# PROC051D_QSPI_Flash_Reference.net
KiCad netlist of a schematic drawn in Altium Designer
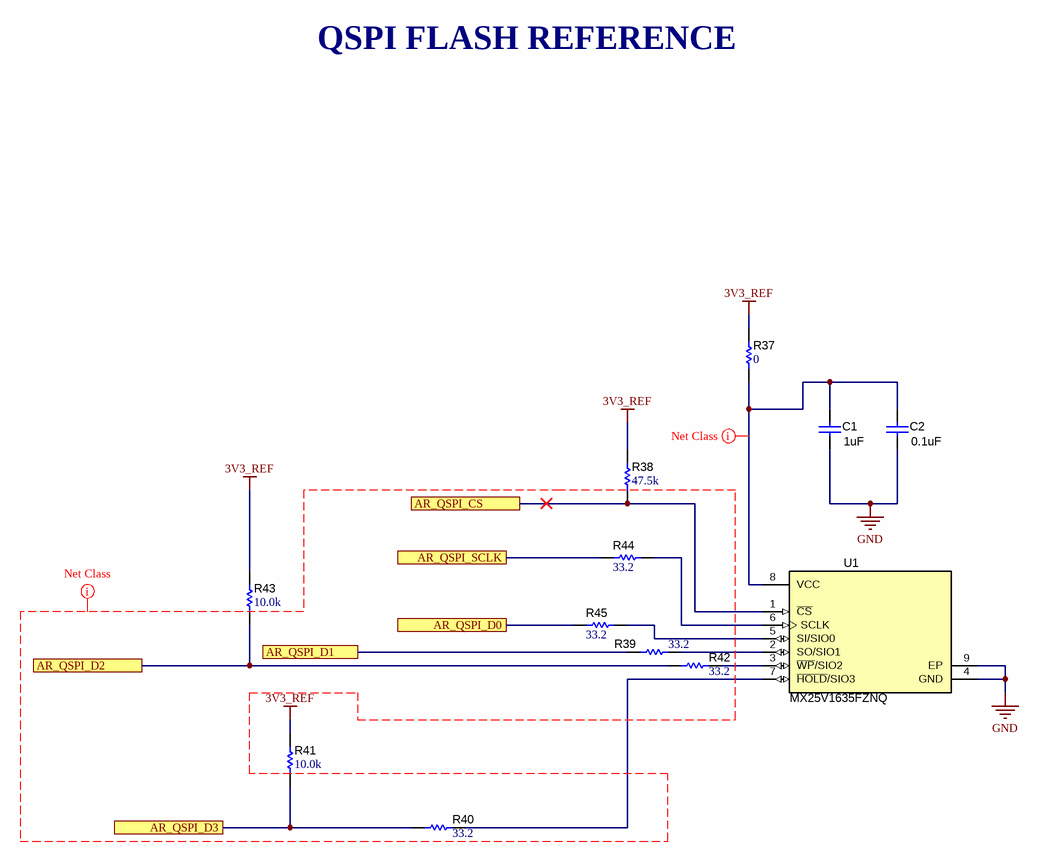
[diagram p0: PROC051D_QSPI_Flash_Reference.SchDoc]

(export (version "E")
  (design (tool "Eeschema 10.0.6"))
  (components
    (comp (ref "C1")
      (value "GCM188R71C105KA64D")
      (footprint "0603")
      (description "CAP, CERM, 1 uF, 16 V, +/- 10%, X7R, AEC-Q200 Grade 1, 0603")
      (fields
        (field (name "MANUFACTURER") "MuRata")
        (field (name "VALUEDISPLAYED") "1uF")
        (field (name "PUBLISHER") "Texas Instruments")
      )
      (libsource (lib "Altium Vault - TI") (part "Capacitor"))
    )
    (comp (ref "C2")
      (value "CGA2B3X7R1H104K050BB")
      (footprint "0402L")
      (description "CAP, CERM, 0.1 uF, 50 V, +/- 10%, X7R, AEC-Q200 Grade 1, 0402")
      (fields
        (field (name "MANUFACTURER") "TDK")
        (field (name "VALUEDISPLAYED") "0.1uF")
        (field (name "PUBLISHER") "Texas Instruments")
      )
      (libsource (lib "Altium Vault - TI") (part "Capacitor"))
    )
    (comp (ref "R37")
      (value "ERJ-2GE0R00X")
      (footprint "0402L")
      (description "RES, 0, 5%, 0.1 W, AEC-Q200 Grade 0, 0402")
      (fields (field (name "MANUFACTURER") "Panasonic") (field (name "VALUEDISPLAYED") "0"))
      (libsource (lib "Altium Vault - TI") (part "Resistor"))
    )
    (comp (ref "R38")
      (value "CRCW040247K5FKED")
      (footprint "0402L")
      (description "RES, 47.5 k, 1%, 0.063 W, AEC-Q200 Grade 0, 0402")
      (fields (field (name "MANUFACTURER") "Vishay-Dale") (field (name "VALUEDISPLAYED") "47.5k"))
      (libsource (lib "Altium Vault - TI") (part "Resistor"))
    )
    (comp (ref "R39")
      (value "CRCW020133R2FNED")
      (footprint "0201_Silk")
      (description "RES, 33.2, 1%, 0.05 W, 0201")
      (fields (field (name "MANUFACTURER") "Vishay-Dale") (field (name "VALUEDISPLAYED") "33.2"))
      (libsource (lib "Altium Vault - TI") (part "Resistor"))
    )
    (comp (ref "R40")
      (value "CRCW020133R2FNED")
      (footprint "0201_Silk")
      (description "RES, 33.2, 1%, 0.05 W, 0201")
      (fields (field (name "MANUFACTURER") "Vishay-Dale") (field (name "VALUEDISPLAYED") "33.2"))
      (libsource (lib "Altium Vault - TI") (part "Resistor"))
    )
    (comp (ref "R41")
      (value "CRCW040210K0FKED")
      (footprint "0402L")
      (description "RES, 10.0 k, 1%, 0.063 W, AEC-Q200 Grade 0, 0402")
      (fields (field (name "MANUFACTURER") "Vishay-Dale") (field (name "VALUEDISPLAYED") "10.0k"))
      (libsource (lib "Altium Vault - TI") (part "Resistor"))
    )
    (comp (ref "R42")
      (value "CRCW020133R2FNED")
      (footprint "0201_Silk")
      (description "RES, 33.2, 1%, 0.05 W, 0201")
      (fields (field (name "MANUFACTURER") "Vishay-Dale") (field (name "VALUEDISPLAYED") "33.2"))
      (libsource (lib "Altium Vault - TI") (part "Resistor"))
    )
    (comp (ref "R43")
      (value "CRCW040210K0FKED")
      (footprint "0402L")
      (description "RES, 10.0 k, 1%, 0.063 W, AEC-Q200 Grade 0, 0402")
      (fields (field (name "MANUFACTURER") "Vishay-Dale") (field (name "VALUEDISPLAYED") "10.0k"))
      (libsource (lib "Altium Vault - TI") (part "Resistor"))
    )
    (comp (ref "R44")
      (value "CRCW020133R2FNED")
      (footprint "0201_Silk")
      (description "RES, 33.2, 1%, 0.05 W, 0201")
      (fields (field (name "MANUFACTURER") "Vishay-Dale") (field (name "VALUEDISPLAYED") "33.2"))
      (libsource (lib "Altium Vault - TI") (part "CMP-0027275-3"))
    )
    (comp (ref "R45")
      (value "CRCW020133R2FNED")
      (footprint "0201_Silk")
      (description "RES, 33.2, 1%, 0.05 W, 0201")
      (fields (field (name "MANUFACTURER") "Vishay-Dale") (field (name "VALUEDISPLAYED") "33.2"))
      (libsource (lib "Altium Vault - TI") (part "Resistor"))
    )
    (comp (ref "U1")
      (value "MX25V1635FZNQ")
      (footprint "WSON-8L_6x5MM_EP")
      (description "2.3V-3.6V, 16M-BIT [x 1/x 2/x 4] CMOS FLASH Memory, WSON-8")
      (fields (field (name "MANUFACTURER") "Macronix International Co., LTD"))
      (libsource (lib "Altium Vault - TI") (part "MX25V1635FZ"))
    )
  )
  (nets
    (net (code "1") (name "/AR_QSPI_CS") (class "Default")
      (node (ref "R38") (pin "1") (pinfunction "1_1") (pintype "passive"))
      (node (ref "U1") (pin "1") (pinfunction "CS_1") (pintype "input"))
    )
    (net (code "2") (name "/AR_QSPI_D0") (class "Default")
      (node (ref "R45") (pin "2") (pinfunction "2_2") (pintype "passive"))
    )
    (net (code "3") (name "/AR_QSPI_D1") (class "Default")
      (node (ref "R39") (pin "1") (pinfunction "1_1") (pintype "passive"))
    )
    (net (code "4") (name "/AR_QSPI_D2") (class "Default")
      (node (ref "R42") (pin "1") (pinfunction "1_1") (pintype "passive"))
      (node (ref "R43") (pin "1") (pinfunction "1_1") (pintype "passive"))
    )
    (net (code "5") (name "/AR_QSPI_D3") (class "Default")
      (node (ref "R40") (pin "2") (pinfunction "2_2") (pintype "passive"))
      (node (ref "R41") (pin "1") (pinfunction "1_1") (pintype "passive"))
    )
    (net (code "6") (name "/AR_QSPI_SCLK") (class "Default")
      (node (ref "R44") (pin "2") (pinfunction "2_2") (pintype "passive"))
    )
    (net (code "7") (name "3V3_REF") (class "Default")
      (node (ref "R37") (pin "1") (pinfunction "1_1") (pintype "passive"))
      (node (ref "R38") (pin "2") (pinfunction "2_2") (pintype "passive"))
      (node (ref "R41") (pin "2") (pinfunction "2_2") (pintype "passive"))
      (node (ref "R43") (pin "2") (pinfunction "2_2") (pintype "passive"))
    )
    (net (code "8") (name "GND") (class "Default")
      (node (ref "C1") (pin "1") (pinfunction "1_1") (pintype "passive"))
      (node (ref "C2") (pin "1") (pinfunction "1_1") (pintype "passive"))
      (node (ref "U1") (pin "4") (pinfunction "GND_4") (pintype "power_in"))
      (node (ref "U1") (pin "9") (pinfunction "EP_9") (pintype "passive"))
    )
    (net (code "9") (name "Net-(U1-SCLK)") (class "Default")
      (node (ref "R44") (pin "1") (pinfunction "1_1") (pintype "passive"))
      (node (ref "U1") (pin "6") (pinfunction "SCLK_6") (pintype "input"))
    )
    (net (code "10") (name "Net-(U1-SI{slash}SIO0)") (class "Default")
      (node (ref "R45") (pin "1") (pinfunction "1_1") (pintype "passive"))
      (node (ref "U1") (pin "5") (pinfunction "SI/SIO0_5") (pintype "bidirectional"))
    )
    (net (code "11") (name "Net-(U1-SO{slash}SIO1)") (class "Default")
      (node (ref "R39") (pin "2") (pinfunction "2_2") (pintype "passive"))
      (node (ref "U1") (pin "2") (pinfunction "SO/SIO1_2") (pintype "bidirectional"))
    )
    (net (code "12") (name "Net-(U1-VCC)") (class "Default")
      (node (ref "C1") (pin "2") (pinfunction "2_2") (pintype "passive"))
      (node (ref "C2") (pin "2") (pinfunction "2_2") (pintype "passive"))
      (node (ref "R37") (pin "2") (pinfunction "2_2") (pintype "passive"))
      (node (ref "U1") (pin "8") (pinfunction "VCC_8") (pintype "power_in"))
    )
    (net (code "13") (name "Net-(U1-~{HOLD}{slash}SIO3)") (class "Default")
      (node (ref "R40") (pin "1") (pinfunction "1_1") (pintype "passive"))
      (node (ref "U1") (pin "7") (pinfunction "~{HOLD}/SIO3_7") (pintype "bidirectional"))
    )
    (net (code "14") (name "Net-(U1-~{WP}{slash}SIO2)") (class "Default")
      (node (ref "R42") (pin "2") (pinfunction "2_2") (pintype "passive"))
      (node (ref "U1") (pin "3") (pinfunction "~{WP}/SIO2_3") (pintype "bidirectional"))
    )
  )
)
